# MDM_V3_LEDPad_D.net
KiCad netlist of a schematic drawn in EAGLE
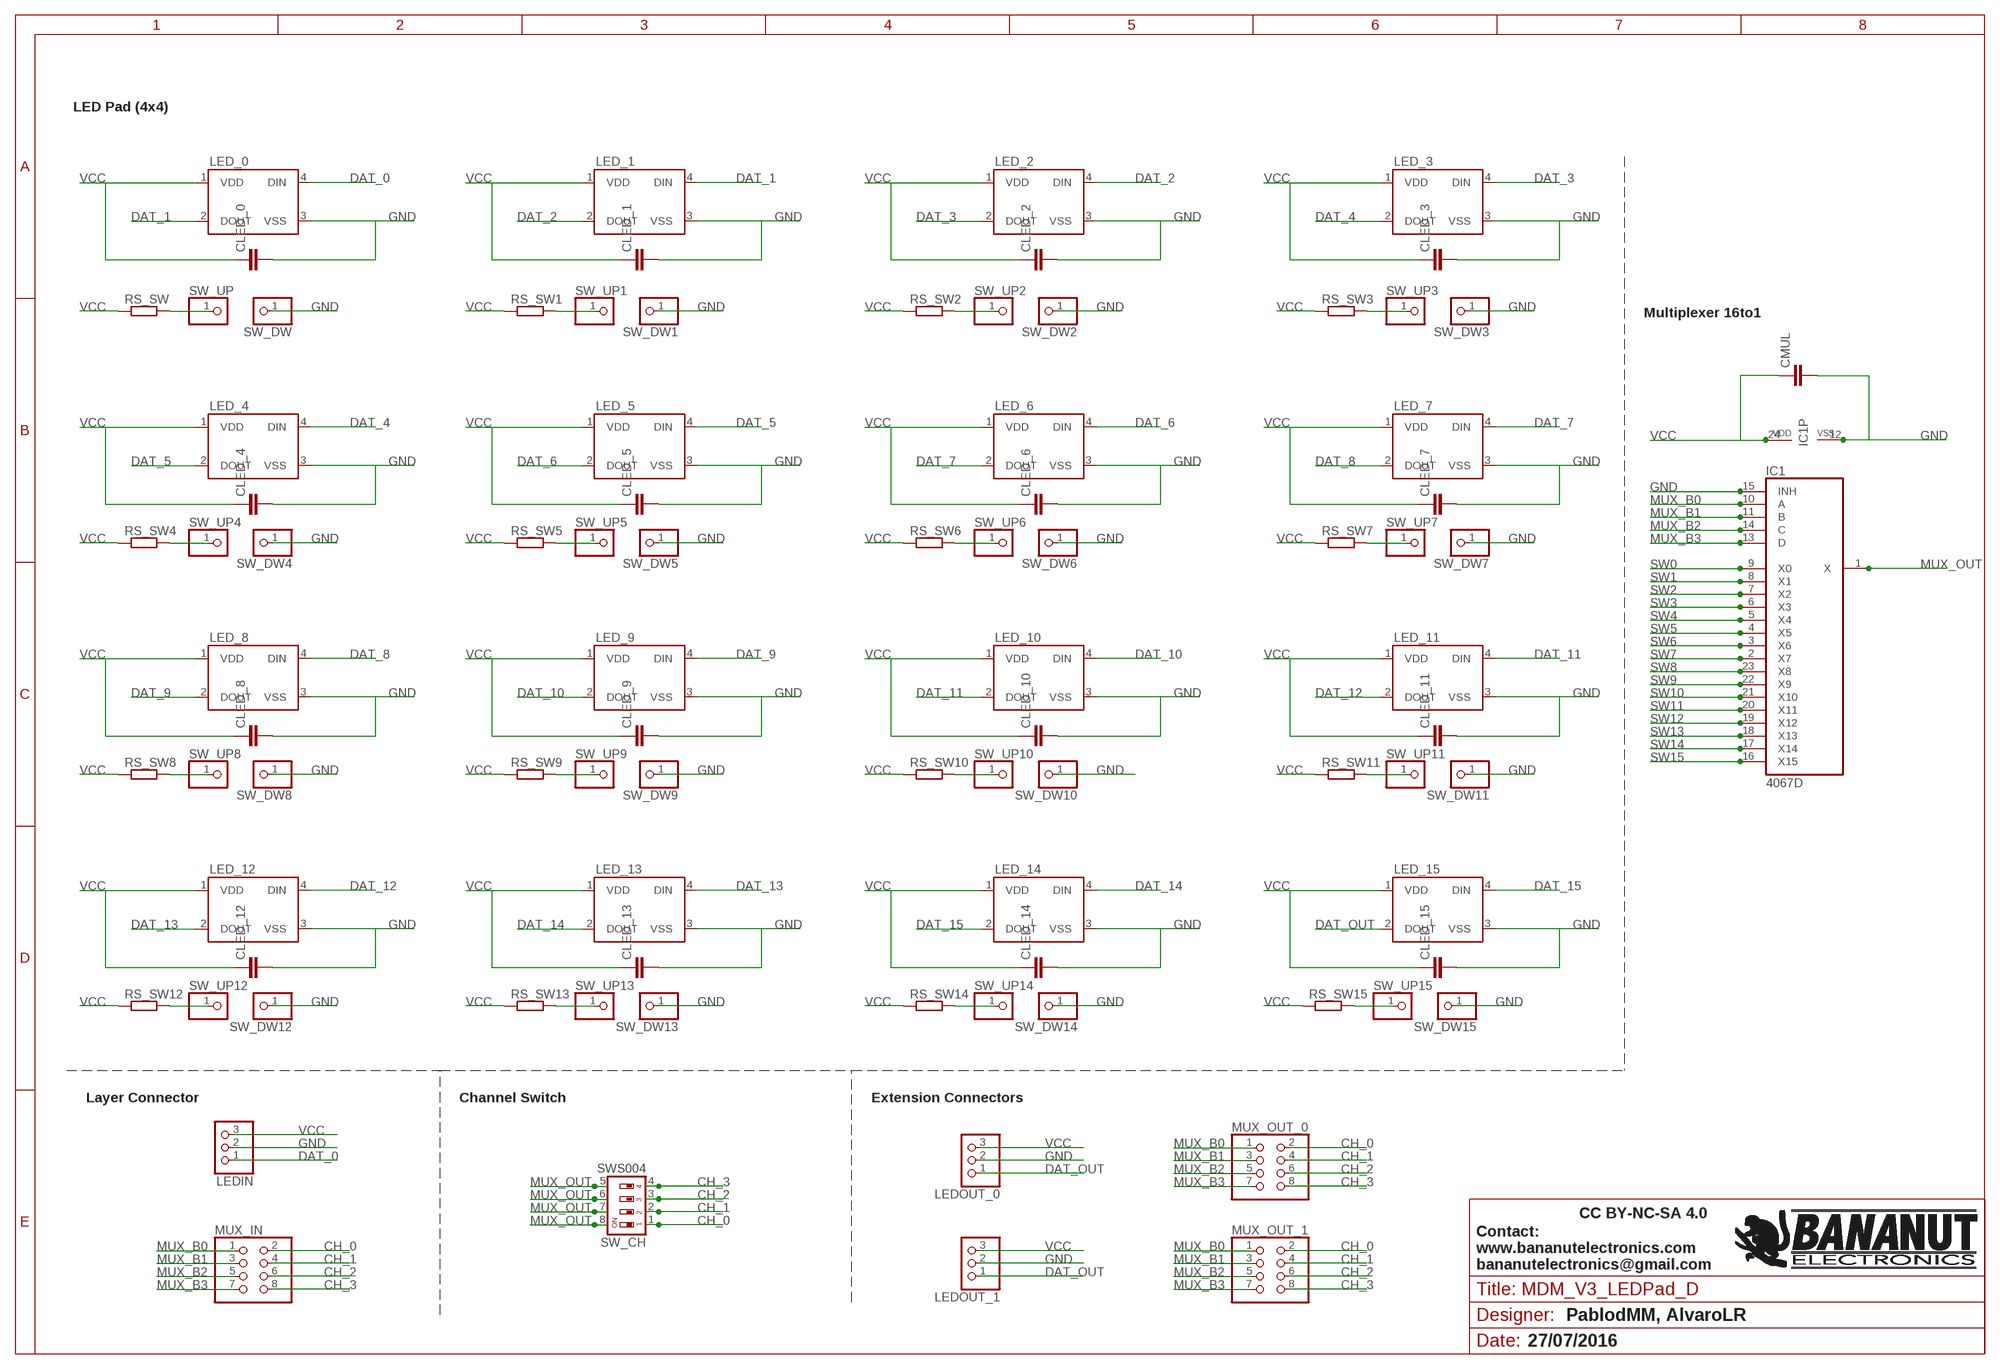
[diagram p0: schematic, sheet 1]

(export (version "E")
  (design (tool "Eeschema 10.0.6"))
  (components
    (comp (ref "CLED_0")
      (value "C-EUC1206K")
      (footprint "eagle-import:C1206K")
      (libsource (lib "eagle-import") (part "C-EUC1206K"))
    )
    (comp (ref "CLED_1")
      (value "C-EUC1206K")
      (footprint "eagle-import:C1206K")
      (libsource (lib "eagle-import") (part "C-EUC1206K"))
    )
    (comp (ref "CLED_2")
      (value "C-EUC1206K")
      (footprint "eagle-import:C1206K")
      (libsource (lib "eagle-import") (part "C-EUC1206K"))
    )
    (comp (ref "CLED_3")
      (value "C-EUC1206K")
      (footprint "eagle-import:C1206K")
      (libsource (lib "eagle-import") (part "C-EUC1206K"))
    )
    (comp (ref "CLED_4")
      (value "C-EUC1206K")
      (footprint "eagle-import:C1206K")
      (libsource (lib "eagle-import") (part "C-EUC1206K"))
    )
    (comp (ref "CLED_5")
      (value "C-EUC1206K")
      (footprint "eagle-import:C1206K")
      (libsource (lib "eagle-import") (part "C-EUC1206K"))
    )
    (comp (ref "CLED_6")
      (value "C-EUC1206K")
      (footprint "eagle-import:C1206K")
      (libsource (lib "eagle-import") (part "C-EUC1206K"))
    )
    (comp (ref "CLED_7")
      (value "C-EUC1206K")
      (footprint "eagle-import:C1206K")
      (libsource (lib "eagle-import") (part "C-EUC1206K"))
    )
    (comp (ref "CLED_8")
      (value "C-EUC1206K")
      (footprint "eagle-import:C1206K")
      (libsource (lib "eagle-import") (part "C-EUC1206K"))
    )
    (comp (ref "CLED_9")
      (value "C-EUC1206K")
      (footprint "eagle-import:C1206K")
      (libsource (lib "eagle-import") (part "C-EUC1206K"))
    )
    (comp (ref "CLED_10")
      (value "C-EUC1206K")
      (footprint "eagle-import:C1206K")
      (libsource (lib "eagle-import") (part "C-EUC1206K"))
    )
    (comp (ref "CLED_11")
      (value "C-EUC1206K")
      (footprint "eagle-import:C1206K")
      (libsource (lib "eagle-import") (part "C-EUC1206K"))
    )
    (comp (ref "CLED_12")
      (value "C-EUC1206K")
      (footprint "eagle-import:C1206K")
      (libsource (lib "eagle-import") (part "C-EUC1206K"))
    )
    (comp (ref "CLED_13")
      (value "C-EUC1206K")
      (footprint "eagle-import:C1206K")
      (libsource (lib "eagle-import") (part "C-EUC1206K"))
    )
    (comp (ref "CLED_14")
      (value "C-EUC1206K")
      (footprint "eagle-import:C1206K")
      (libsource (lib "eagle-import") (part "C-EUC1206K"))
    )
    (comp (ref "CLED_15")
      (value "C-EUC1206K")
      (footprint "eagle-import:C1206K")
      (libsource (lib "eagle-import") (part "C-EUC1206K"))
    )
    (comp (ref "CMUL")
      (value "C-EUC1206K")
      (footprint "eagle-import:C1206K")
      (libsource (lib "eagle-import") (part "C-EUC1206K"))
    )
    (comp (ref "IC1")
      (value "4067D")
      (footprint "eagle-import:SO24W")
      (libsource (lib "eagle-import") (part "4067D"))
    )
    (comp (ref "LEDIN")
      (value "PINHD-1X3")
      (footprint "eagle-import:1X03")
      (libsource (lib "eagle-import") (part "PINHD-1X3"))
    )
    (comp (ref "LEDOUT_0")
      (value "PINHD-1X3")
      (footprint "eagle-import:1X03")
      (libsource (lib "eagle-import") (part "PINHD-1X3"))
    )
    (comp (ref "LEDOUT_1")
      (value "PINHD-1X3")
      (footprint "eagle-import:1X03")
      (libsource (lib "eagle-import") (part "PINHD-1X3"))
    )
    (comp (ref "LED_0")
      (value "WS2812B")
      (footprint "eagle-import:WS2812B")
      (libsource (lib "eagle-import") (part "WS2812B"))
    )
    (comp (ref "LED_1")
      (value "WS2812B")
      (footprint "eagle-import:WS2812B")
      (libsource (lib "eagle-import") (part "WS2812B"))
    )
    (comp (ref "LED_2")
      (value "WS2812B")
      (footprint "eagle-import:WS2812B")
      (libsource (lib "eagle-import") (part "WS2812B"))
    )
    (comp (ref "LED_3")
      (value "WS2812B")
      (footprint "eagle-import:WS2812B")
      (libsource (lib "eagle-import") (part "WS2812B"))
    )
    (comp (ref "LED_4")
      (value "WS2812B")
      (footprint "eagle-import:WS2812B")
      (libsource (lib "eagle-import") (part "WS2812B"))
    )
    (comp (ref "LED_5")
      (value "WS2812B")
      (footprint "eagle-import:WS2812B")
      (libsource (lib "eagle-import") (part "WS2812B"))
    )
    (comp (ref "LED_6")
      (value "WS2812B")
      (footprint "eagle-import:WS2812B")
      (libsource (lib "eagle-import") (part "WS2812B"))
    )
    (comp (ref "LED_7")
      (value "WS2812B")
      (footprint "eagle-import:WS2812B")
      (libsource (lib "eagle-import") (part "WS2812B"))
    )
    (comp (ref "LED_8")
      (value "WS2812B")
      (footprint "eagle-import:WS2812B")
      (libsource (lib "eagle-import") (part "WS2812B"))
    )
    (comp (ref "LED_9")
      (value "WS2812B")
      (footprint "eagle-import:WS2812B")
      (libsource (lib "eagle-import") (part "WS2812B"))
    )
    (comp (ref "LED_10")
      (value "WS2812B")
      (footprint "eagle-import:WS2812B")
      (libsource (lib "eagle-import") (part "WS2812B"))
    )
    (comp (ref "LED_11")
      (value "WS2812B")
      (footprint "eagle-import:WS2812B")
      (libsource (lib "eagle-import") (part "WS2812B"))
    )
    (comp (ref "LED_12")
      (value "WS2812B")
      (footprint "eagle-import:WS2812B")
      (libsource (lib "eagle-import") (part "WS2812B"))
    )
    (comp (ref "LED_13")
      (value "WS2812B")
      (footprint "eagle-import:WS2812B")
      (libsource (lib "eagle-import") (part "WS2812B"))
    )
    (comp (ref "LED_14")
      (value "WS2812B")
      (footprint "eagle-import:WS2812B")
      (libsource (lib "eagle-import") (part "WS2812B"))
    )
    (comp (ref "LED_15")
      (value "WS2812B")
      (footprint "eagle-import:WS2812B")
      (libsource (lib "eagle-import") (part "WS2812B"))
    )
    (comp (ref "MUX_IN")
      (value "PINHD-2X4")
      (footprint "eagle-import:2X04")
      (libsource (lib "eagle-import") (part "PINHD-2X4"))
    )
    (comp (ref "MUX_OUT_0")
      (value "PINHD-2X4")
      (footprint "eagle-import:2X04")
      (libsource (lib "eagle-import") (part "PINHD-2X4"))
    )
    (comp (ref "MUX_OUT_1")
      (value "PINHD-2X4")
      (footprint "eagle-import:2X04")
      (libsource (lib "eagle-import") (part "PINHD-2X4"))
    )
    (comp (ref "RS_SW")
      (value "R-EU_R1206")
      (footprint "eagle-import:R1206")
      (libsource (lib "eagle-import") (part "R-EU_R1206"))
    )
    (comp (ref "RS_SW1")
      (value "R-EU_R1206")
      (footprint "eagle-import:R1206")
      (libsource (lib "eagle-import") (part "R-EU_R1206"))
    )
    (comp (ref "RS_SW2")
      (value "R-EU_R1206")
      (footprint "eagle-import:R1206")
      (libsource (lib "eagle-import") (part "R-EU_R1206"))
    )
    (comp (ref "RS_SW3")
      (value "R-EU_R1206")
      (footprint "eagle-import:R1206")
      (libsource (lib "eagle-import") (part "R-EU_R1206"))
    )
    (comp (ref "RS_SW4")
      (value "R-EU_R1206")
      (footprint "eagle-import:R1206")
      (libsource (lib "eagle-import") (part "R-EU_R1206"))
    )
    (comp (ref "RS_SW5")
      (value "R-EU_R1206")
      (footprint "eagle-import:R1206")
      (libsource (lib "eagle-import") (part "R-EU_R1206"))
    )
    (comp (ref "RS_SW6")
      (value "R-EU_R1206")
      (footprint "eagle-import:R1206")
      (libsource (lib "eagle-import") (part "R-EU_R1206"))
    )
    (comp (ref "RS_SW7")
      (value "R-EU_R1206")
      (footprint "eagle-import:R1206")
      (libsource (lib "eagle-import") (part "R-EU_R1206"))
    )
    (comp (ref "RS_SW8")
      (value "R-EU_R1206")
      (footprint "eagle-import:R1206")
      (libsource (lib "eagle-import") (part "R-EU_R1206"))
    )
    (comp (ref "RS_SW9")
      (value "R-EU_R1206")
      (footprint "eagle-import:R1206")
      (libsource (lib "eagle-import") (part "R-EU_R1206"))
    )
    (comp (ref "RS_SW10")
      (value "R-EU_R1206")
      (footprint "eagle-import:R1206")
      (libsource (lib "eagle-import") (part "R-EU_R1206"))
    )
    (comp (ref "RS_SW11")
      (value "R-EU_R1206")
      (footprint "eagle-import:R1206")
      (libsource (lib "eagle-import") (part "R-EU_R1206"))
    )
    (comp (ref "RS_SW12")
      (value "R-EU_R1206")
      (footprint "eagle-import:R1206")
      (libsource (lib "eagle-import") (part "R-EU_R1206"))
    )
    (comp (ref "RS_SW13")
      (value "R-EU_R1206")
      (footprint "eagle-import:R1206")
      (libsource (lib "eagle-import") (part "R-EU_R1206"))
    )
    (comp (ref "RS_SW14")
      (value "R-EU_R1206")
      (footprint "eagle-import:R1206")
      (libsource (lib "eagle-import") (part "R-EU_R1206"))
    )
    (comp (ref "RS_SW15")
      (value "R-EU_R1206")
      (footprint "eagle-import:R1206")
      (libsource (lib "eagle-import") (part "R-EU_R1206"))
    )
    (comp (ref "SW_CH")
      (value "SWS004")
      (footprint "eagle-import:SMS-004")
      (libsource (lib "eagle-import") (part "SWS004"))
    )
    (comp (ref "SW_DW")
      (value "PINHD-1X1CB")
      (footprint "eagle-import:1X01-CLEANBIG")
      (libsource (lib "eagle-import") (part "PINHD-1X1CB"))
    )
    (comp (ref "SW_DW1")
      (value "PINHD-1X1CB")
      (footprint "eagle-import:1X01-CLEANBIG")
      (libsource (lib "eagle-import") (part "PINHD-1X1CB"))
    )
    (comp (ref "SW_DW2")
      (value "PINHD-1X1CB")
      (footprint "eagle-import:1X01-CLEANBIG")
      (libsource (lib "eagle-import") (part "PINHD-1X1CB"))
    )
    (comp (ref "SW_DW3")
      (value "PINHD-1X1CB")
      (footprint "eagle-import:1X01-CLEANBIG")
      (libsource (lib "eagle-import") (part "PINHD-1X1CB"))
    )
    (comp (ref "SW_DW4")
      (value "PINHD-1X1CB")
      (footprint "eagle-import:1X01-CLEANBIG")
      (libsource (lib "eagle-import") (part "PINHD-1X1CB"))
    )
    (comp (ref "SW_DW5")
      (value "PINHD-1X1CB")
      (footprint "eagle-import:1X01-CLEANBIG")
      (libsource (lib "eagle-import") (part "PINHD-1X1CB"))
    )
    (comp (ref "SW_DW6")
      (value "PINHD-1X1CB")
      (footprint "eagle-import:1X01-CLEANBIG")
      (libsource (lib "eagle-import") (part "PINHD-1X1CB"))
    )
    (comp (ref "SW_DW7")
      (value "PINHD-1X1CB")
      (footprint "eagle-import:1X01-CLEANBIG")
      (libsource (lib "eagle-import") (part "PINHD-1X1CB"))
    )
    (comp (ref "SW_DW8")
      (value "PINHD-1X1CB")
      (footprint "eagle-import:1X01-CLEANBIG")
      (libsource (lib "eagle-import") (part "PINHD-1X1CB"))
    )
    (comp (ref "SW_DW9")
      (value "PINHD-1X1CB")
      (footprint "eagle-import:1X01-CLEANBIG")
      (libsource (lib "eagle-import") (part "PINHD-1X1CB"))
    )
    (comp (ref "SW_DW10")
      (value "PINHD-1X1CB")
      (footprint "eagle-import:1X01-CLEANBIG")
      (libsource (lib "eagle-import") (part "PINHD-1X1CB"))
    )
    (comp (ref "SW_DW11")
      (value "PINHD-1X1CB")
      (footprint "eagle-import:1X01-CLEANBIG")
      (libsource (lib "eagle-import") (part "PINHD-1X1CB"))
    )
    (comp (ref "SW_DW12")
      (value "PINHD-1X1CB")
      (footprint "eagle-import:1X01-CLEANBIG")
      (libsource (lib "eagle-import") (part "PINHD-1X1CB"))
    )
    (comp (ref "SW_DW13")
      (value "PINHD-1X1CB")
      (footprint "eagle-import:1X01-CLEANBIG")
      (libsource (lib "eagle-import") (part "PINHD-1X1CB"))
    )
    (comp (ref "SW_DW14")
      (value "PINHD-1X1CB")
      (footprint "eagle-import:1X01-CLEANBIG")
      (libsource (lib "eagle-import") (part "PINHD-1X1CB"))
    )
    (comp (ref "SW_DW15")
      (value "PINHD-1X1CB")
      (footprint "eagle-import:1X01-CLEANBIG")
      (libsource (lib "eagle-import") (part "PINHD-1X1CB"))
    )
    (comp (ref "SW_UP")
      (value "PINHD-1X1CB")
      (footprint "eagle-import:1X01-CLEANBIG")
      (libsource (lib "eagle-import") (part "PINHD-1X1CB"))
    )
    (comp (ref "SW_UP1")
      (value "PINHD-1X1CB")
      (footprint "eagle-import:1X01-CLEANBIG")
      (libsource (lib "eagle-import") (part "PINHD-1X1CB"))
    )
    (comp (ref "SW_UP2")
      (value "PINHD-1X1CB")
      (footprint "eagle-import:1X01-CLEANBIG")
      (libsource (lib "eagle-import") (part "PINHD-1X1CB"))
    )
    (comp (ref "SW_UP3")
      (value "PINHD-1X1CB")
      (footprint "eagle-import:1X01-CLEANBIG")
      (libsource (lib "eagle-import") (part "PINHD-1X1CB"))
    )
    (comp (ref "SW_UP4")
      (value "PINHD-1X1CB")
      (footprint "eagle-import:1X01-CLEANBIG")
      (libsource (lib "eagle-import") (part "PINHD-1X1CB"))
    )
    (comp (ref "SW_UP5")
      (value "PINHD-1X1CB")
      (footprint "eagle-import:1X01-CLEANBIG")
      (libsource (lib "eagle-import") (part "PINHD-1X1CB"))
    )
    (comp (ref "SW_UP6")
      (value "PINHD-1X1CB")
      (footprint "eagle-import:1X01-CLEANBIG")
      (libsource (lib "eagle-import") (part "PINHD-1X1CB"))
    )
    (comp (ref "SW_UP7")
      (value "PINHD-1X1CB")
      (footprint "eagle-import:1X01-CLEANBIG")
      (libsource (lib "eagle-import") (part "PINHD-1X1CB"))
    )
    (comp (ref "SW_UP8")
      (value "PINHD-1X1CB")
      (footprint "eagle-import:1X01-CLEANBIG")
      (libsource (lib "eagle-import") (part "PINHD-1X1CB"))
    )
    (comp (ref "SW_UP9")
      (value "PINHD-1X1CB")
      (footprint "eagle-import:1X01-CLEANBIG")
      (libsource (lib "eagle-import") (part "PINHD-1X1CB"))
    )
    (comp (ref "SW_UP10")
      (value "PINHD-1X1CB")
      (footprint "eagle-import:1X01-CLEANBIG")
      (libsource (lib "eagle-import") (part "PINHD-1X1CB"))
    )
    (comp (ref "SW_UP11")
      (value "PINHD-1X1CB")
      (footprint "eagle-import:1X01-CLEANBIG")
      (libsource (lib "eagle-import") (part "PINHD-1X1CB"))
    )
    (comp (ref "SW_UP12")
      (value "PINHD-1X1CB")
      (footprint "eagle-import:1X01-CLEANBIG")
      (libsource (lib "eagle-import") (part "PINHD-1X1CB"))
    )
    (comp (ref "SW_UP13")
      (value "PINHD-1X1CB")
      (footprint "eagle-import:1X01-CLEANBIG")
      (libsource (lib "eagle-import") (part "PINHD-1X1CB"))
    )
    (comp (ref "SW_UP14")
      (value "PINHD-1X1CB")
      (footprint "eagle-import:1X01-CLEANBIG")
      (libsource (lib "eagle-import") (part "PINHD-1X1CB"))
    )
    (comp (ref "SW_UP15")
      (value "PINHD-1X1CB")
      (footprint "eagle-import:1X01-CLEANBIG")
      (libsource (lib "eagle-import") (part "PINHD-1X1CB"))
    )
  )
  (nets
    (net (code "1") (name "/CH_0") (class "Default")
      (node (ref "MUX_IN") (pin "2") (pinfunction "2_2") (pintype "passive"))
      (node (ref "MUX_OUT_0") (pin "2") (pinfunction "2_2") (pintype "passive"))
      (node (ref "MUX_OUT_1") (pin "2") (pinfunction "2_2") (pintype "passive"))
      (node (ref "SW_CH") (pin "1") (pinfunction "1_1") (pintype "passive"))
    )
    (net (code "2") (name "/CH_1") (class "Default")
      (node (ref "MUX_IN") (pin "4") (pinfunction "4_4") (pintype "passive"))
      (node (ref "MUX_OUT_0") (pin "4") (pinfunction "4_4") (pintype "passive"))
      (node (ref "MUX_OUT_1") (pin "4") (pinfunction "4_4") (pintype "passive"))
      (node (ref "SW_CH") (pin "2") (pinfunction "2_2") (pintype "passive"))
    )
    (net (code "3") (name "/CH_2") (class "Default")
      (node (ref "MUX_IN") (pin "6") (pinfunction "6_6") (pintype "passive"))
      (node (ref "MUX_OUT_0") (pin "6") (pinfunction "6_6") (pintype "passive"))
      (node (ref "MUX_OUT_1") (pin "6") (pinfunction "6_6") (pintype "passive"))
      (node (ref "SW_CH") (pin "3") (pinfunction "3_3") (pintype "passive"))
    )
    (net (code "4") (name "/CH_3") (class "Default")
      (node (ref "MUX_IN") (pin "8") (pinfunction "8_8") (pintype "passive"))
      (node (ref "MUX_OUT_0") (pin "8") (pinfunction "8_8") (pintype "passive"))
      (node (ref "MUX_OUT_1") (pin "8") (pinfunction "8_8") (pintype "passive"))
      (node (ref "SW_CH") (pin "4") (pinfunction "4_4") (pintype "passive"))
    )
    (net (code "5") (name "/DAT_0") (class "Default")
      (node (ref "LEDIN") (pin "1") (pinfunction "1_1") (pintype "passive"))
      (node (ref "LED_0") (pin "4") (pinfunction "DIN_4") (pintype "input"))
    )
    (net (code "6") (name "/DAT_1") (class "Default")
      (node (ref "LED_0") (pin "2") (pinfunction "DOUT_2") (pintype "output"))
      (node (ref "LED_1") (pin "4") (pinfunction "DIN_4") (pintype "input"))
    )
    (net (code "7") (name "/DAT_2") (class "Default")
      (node (ref "LED_1") (pin "2") (pinfunction "DOUT_2") (pintype "output"))
      (node (ref "LED_2") (pin "4") (pinfunction "DIN_4") (pintype "input"))
    )
    (net (code "8") (name "/DAT_3") (class "Default")
      (node (ref "LED_2") (pin "2") (pinfunction "DOUT_2") (pintype "output"))
      (node (ref "LED_3") (pin "4") (pinfunction "DIN_4") (pintype "input"))
    )
    (net (code "9") (name "/DAT_4") (class "Default")
      (node (ref "LED_3") (pin "2") (pinfunction "DOUT_2") (pintype "output"))
      (node (ref "LED_4") (pin "4") (pinfunction "DIN_4") (pintype "input"))
    )
    (net (code "10") (name "/DAT_5") (class "Default")
      (node (ref "LED_4") (pin "2") (pinfunction "DOUT_2") (pintype "output"))
      (node (ref "LED_5") (pin "4") (pinfunction "DIN_4") (pintype "input"))
    )
    (net (code "11") (name "/DAT_6") (class "Default")
      (node (ref "LED_5") (pin "2") (pinfunction "DOUT_2") (pintype "output"))
      (node (ref "LED_6") (pin "4") (pinfunction "DIN_4") (pintype "input"))
    )
    (net (code "12") (name "/DAT_7") (class "Default")
      (node (ref "LED_6") (pin "2") (pinfunction "DOUT_2") (pintype "output"))
      (node (ref "LED_7") (pin "4") (pinfunction "DIN_4") (pintype "input"))
    )
    (net (code "13") (name "/DAT_8") (class "Default")
      (node (ref "LED_7") (pin "2") (pinfunction "DOUT_2") (pintype "output"))
      (node (ref "LED_8") (pin "4") (pinfunction "DIN_4") (pintype "input"))
    )
    (net (code "14") (name "/DAT_9") (class "Default")
      (node (ref "LED_8") (pin "2") (pinfunction "DOUT_2") (pintype "output"))
      (node (ref "LED_9") (pin "4") (pinfunction "DIN_4") (pintype "input"))
    )
    (net (code "15") (name "/DAT_10") (class "Default")
      (node (ref "LED_10") (pin "4") (pinfunction "DIN_4") (pintype "input"))
      (node (ref "LED_9") (pin "2") (pinfunction "DOUT_2") (pintype "output"))
    )
    (net (code "16") (name "/DAT_11") (class "Default")
      (node (ref "LED_10") (pin "2") (pinfunction "DOUT_2") (pintype "output"))
      (node (ref "LED_11") (pin "4") (pinfunction "DIN_4") (pintype "input"))
    )
    (net (code "17") (name "/DAT_12") (class "Default")
      (node (ref "LED_11") (pin "2") (pinfunction "DOUT_2") (pintype "output"))
      (node (ref "LED_12") (pin "4") (pinfunction "DIN_4") (pintype "input"))
    )
    (net (code "18") (name "/DAT_13") (class "Default")
      (node (ref "LED_12") (pin "2") (pinfunction "DOUT_2") (pintype "output"))
      (node (ref "LED_13") (pin "4") (pinfunction "DIN_4") (pintype "input"))
    )
    (net (code "19") (name "/DAT_14") (class "Default")
      (node (ref "LED_13") (pin "2") (pinfunction "DOUT_2") (pintype "output"))
      (node (ref "LED_14") (pin "4") (pinfunction "DIN_4") (pintype "input"))
    )
    (net (code "20") (name "/DAT_15") (class "Default")
      (node (ref "LED_14") (pin "2") (pinfunction "DOUT_2") (pintype "output"))
      (node (ref "LED_15") (pin "4") (pinfunction "DIN_4") (pintype "input"))
    )
    (net (code "21") (name "/DAT_OUT") (class "Default")
      (node (ref "LEDOUT_0") (pin "1") (pinfunction "1_1") (pintype "passive"))
      (node (ref "LEDOUT_1") (pin "1") (pinfunction "1_1") (pintype "passive"))
      (node (ref "LED_15") (pin "2") (pinfunction "DOUT_2") (pintype "output"))
    )
    (net (code "22") (name "/GND") (class "Default")
      (node (ref "CLED_0") (pin "2") (pinfunction "2_2") (pintype "passive"))
      (node (ref "CLED_1") (pin "2") (pinfunction "2_2") (pintype "passive"))
      (node (ref "CLED_10") (pin "2") (pinfunction "2_2") (pintype "passive"))
      (node (ref "CLED_11") (pin "2") (pinfunction "2_2") (pintype "passive"))
      (node (ref "CLED_12") (pin "2") (pinfunction "2_2") (pintype "passive"))
      (node (ref "CLED_13") (pin "2") (pinfunction "2_2") (pintype "passive"))
      (node (ref "CLED_14") (pin "2") (pinfunction "2_2") (pintype "passive"))
      (node (ref "CLED_15") (pin "2") (pinfunction "2_2") (pintype "passive"))
      (node (ref "CLED_2") (pin "2") (pinfunction "2_2") (pintype "passive"))
      (node (ref "CLED_3") (pin "2") (pinfunction "2_2") (pintype "passive"))
      (node (ref "CLED_4") (pin "2") (pinfunction "2_2") (pintype "passive"))
      (node (ref "CLED_5") (pin "2") (pinfunction "2_2") (pintype "passive"))
      (node (ref "CLED_6") (pin "2") (pinfunction "2_2") (pintype "passive"))
      (node (ref "CLED_7") (pin "2") (pinfunction "2_2") (pintype "passive"))
      (node (ref "CLED_8") (pin "2") (pinfunction "2_2") (pintype "passive"))
      (node (ref "CLED_9") (pin "2") (pinfunction "2_2") (pintype "passive"))
      (node (ref "CMUL") (pin "2") (pinfunction "2_2") (pintype "passive"))
      (node (ref "IC1") (pin "12") (pinfunction "VSS_12") (pintype "power_in"))
      (node (ref "IC1") (pin "15") (pinfunction "INH_15") (pintype "input"))
      (node (ref "LEDIN") (pin "2") (pinfunction "2_2") (pintype "passive"))
      (node (ref "LEDOUT_0") (pin "2") (pinfunction "2_2") (pintype "passive"))
      (node (ref "LEDOUT_1") (pin "2") (pinfunction "2_2") (pintype "passive"))
      (node (ref "LED_0") (pin "3") (pinfunction "VSS_3") (pintype "power_in"))
      (node (ref "LED_1") (pin "3") (pinfunction "VSS_3") (pintype "power_in"))
      (node (ref "LED_10") (pin "3") (pinfunction "VSS_3") (pintype "power_in"))
      (node (ref "LED_11") (pin "3") (pinfunction "VSS_3") (pintype "power_in"))
      (node (ref "LED_12") (pin "3") (pinfunction "VSS_3") (pintype "power_in"))
      (node (ref "LED_13") (pin "3") (pinfunction "VSS_3") (pintype "power_in"))
      (node (ref "LED_14") (pin "3") (pinfunction "VSS_3") (pintype "power_in"))
      (node (ref "LED_15") (pin "3") (pinfunction "VSS_3") (pintype "power_in"))
      (node (ref "LED_2") (pin "3") (pinfunction "VSS_3") (pintype "power_in"))
      (node (ref "LED_3") (pin "3") (pinfunction "VSS_3") (pintype "power_in"))
      (node (ref "LED_4") (pin "3") (pinfunction "VSS_3") (pintype "power_in"))
      (node (ref "LED_5") (pin "3") (pinfunction "VSS_3") (pintype "power_in"))
      (node (ref "LED_6") (pin "3") (pinfunction "VSS_3") (pintype "power_in"))
      (node (ref "LED_7") (pin "3") (pinfunction "VSS_3") (pintype "power_in"))
      (node (ref "LED_8") (pin "3") (pinfunction "VSS_3") (pintype "power_in"))
      (node (ref "LED_9") (pin "3") (pinfunction "VSS_3") (pintype "power_in"))
      (node (ref "SW_DW") (pin "1") (pinfunction "1_1") (pintype "passive"))
      (node (ref "SW_DW1") (pin "1") (pinfunction "1_1") (pintype "passive"))
      (node (ref "SW_DW10") (pin "1") (pinfunction "1_1") (pintype "passive"))
      (node (ref "SW_DW11") (pin "1") (pinfunction "1_1") (pintype "passive"))
      (node (ref "SW_DW12") (pin "1") (pinfunction "1_1") (pintype "passive"))
      (node (ref "SW_DW13") (pin "1") (pinfunction "1_1") (pintype "passive"))
      (node (ref "SW_DW14") (pin "1") (pinfunction "1_1") (pintype "passive"))
      (node (ref "SW_DW15") (pin "1") (pinfunction "1_1") (pintype "passive"))
      (node (ref "SW_DW2") (pin "1") (pinfunction "1_1") (pintype "passive"))
      (node (ref "SW_DW3") (pin "1") (pinfunction "1_1") (pintype "passive"))
      (node (ref "SW_DW4") (pin "1") (pinfunction "1_1") (pintype "passive"))
      (node (ref "SW_DW5") (pin "1") (pinfunction "1_1") (pintype "passive"))
      (node (ref "SW_DW6") (pin "1") (pinfunction "1_1") (pintype "passive"))
      (node (ref "SW_DW7") (pin "1") (pinfunction "1_1") (pintype "passive"))
      (node (ref "SW_DW8") (pin "1") (pinfunction "1_1") (pintype "passive"))
      (node (ref "SW_DW9") (pin "1") (pinfunction "1_1") (pintype "passive"))
    )
    (net (code "23") (name "/MUX_B0") (class "Default")
      (node (ref "IC1") (pin "10") (pinfunction "A_10") (pintype "input"))
      (node (ref "MUX_IN") (pin "1") (pinfunction "1_1") (pintype "passive"))
      (node (ref "MUX_OUT_0") (pin "1") (pinfunction "1_1") (pintype "passive"))
      (node (ref "MUX_OUT_1") (pin "1") (pinfunction "1_1") (pintype "passive"))
    )
    (net (code "24") (name "/MUX_B1") (class "Default")
      (node (ref "IC1") (pin "11") (pinfunction "B_11") (pintype "input"))
      (node (ref "MUX_IN") (pin "3") (pinfunction "3_3") (pintype "passive"))
      (node (ref "MUX_OUT_0") (pin "3") (pinfunction "3_3") (pintype "passive"))
      (node (ref "MUX_OUT_1") (pin "3") (pinfunction "3_3") (pintype "passive"))
    )
    (net (code "25") (name "/MUX_B2") (class "Default")
      (node (ref "IC1") (pin "14") (pinfunction "C_14") (pintype "input"))
      (node (ref "MUX_IN") (pin "5") (pinfunction "5_5") (pintype "passive"))
      (node (ref "MUX_OUT_0") (pin "5") (pinfunction "5_5") (pintype "passive"))
      (node (ref "MUX_OUT_1") (pin "5") (pinfunction "5_5") (pintype "passive"))
    )
    (net (code "26") (name "/MUX_B3") (class "Default")
      (node (ref "IC1") (pin "13") (pinfunction "D_13") (pintype "input"))
      (node (ref "MUX_IN") (pin "7") (pinfunction "7_7") (pintype "passive"))
      (node (ref "MUX_OUT_0") (pin "7") (pinfunction "7_7") (pintype "passive"))
      (node (ref "MUX_OUT_1") (pin "7") (pinfunction "7_7") (pintype "passive"))
    )
    (net (code "27") (name "/MUX_OUT") (class "Default")
      (node (ref "IC1") (pin "1") (pinfunction "X_1") (pintype "output"))
      (node (ref "SW_CH") (pin "5") (pinfunction "5_5") (pintype "passive"))
      (node (ref "SW_CH") (pin "6") (pinfunction "6_6") (pintype "passive"))
      (node (ref "SW_CH") (pin "7") (pinfunction "7_7") (pintype "passive"))
      (node (ref "SW_CH") (pin "8") (pinfunction "8_8") (pintype "passive"))
    )
    (net (code "28") (name "/SW0") (class "Default")
      (node (ref "IC1") (pin "9") (pinfunction "X0_9") (pintype "input"))
      (node (ref "RS_SW") (pin "2") (pinfunction "2_2") (pintype "passive"))
      (node (ref "SW_UP") (pin "1") (pinfunction "1_1") (pintype "passive"))
    )
    (net (code "29") (name "/SW1") (class "Default")
      (node (ref "IC1") (pin "8") (pinfunction "X1_8") (pintype "input"))
      (node (ref "RS_SW1") (pin "2") (pinfunction "2_2") (pintype "passive"))
      (node (ref "SW_UP1") (pin "1") (pinfunction "1_1") (pintype "passive"))
    )
    (net (code "30") (name "/SW2") (class "Default")
      (node (ref "IC1") (pin "7") (pinfunction "X2_7") (pintype "input"))
      (node (ref "RS_SW2") (pin "2") (pinfunction "2_2") (pintype "passive"))
      (node (ref "SW_UP2") (pin "1") (pinfunction "1_1") (pintype "passive"))
    )
    (net (code "31") (name "/SW3") (class "Default")
      (node (ref "IC1") (pin "6") (pinfunction "X3_6") (pintype "input"))
      (node (ref "RS_SW3") (pin "2") (pinfunction "2_2") (pintype "passive"))
      (node (ref "SW_UP3") (pin "1") (pinfunction "1_1") (pintype "passive"))
    )
    (net (code "32") (name "/SW4") (class "Default")
      (node (ref "IC1") (pin "5") (pinfunction "X4_5") (pintype "input"))
      (node (ref "RS_SW4") (pin "2") (pinfunction "2_2") (pintype "passive"))
      (node (ref "SW_UP4") (pin "1") (pinfunction "1_1") (pintype "passive"))
    )
    (net (code "33") (name "/SW5") (class "Default")
      (node (ref "IC1") (pin "4") (pinfunction "X5_4") (pintype "input"))
      (node (ref "RS_SW5") (pin "2") (pinfunction "2_2") (pintype "passive"))
      (node (ref "SW_UP5") (pin "1") (pinfunction "1_1") (pintype "passive"))
    )
    (net (code "34") (name "/SW6") (class "Default")
      (node (ref "IC1") (pin "3") (pinfunction "X6_3") (pintype "input"))
      (node (ref "RS_SW6") (pin "2") (pinfunction "2_2") (pintype "passive"))
      (node (ref "SW_UP6") (pin "1") (pinfunction "1_1") (pintype "passive"))
    )
    (net (code "35") (name "/SW7") (class "Default")
      (node (ref "IC1") (pin "2") (pinfunction "X7_2") (pintype "input"))
      (node (ref "RS_SW7") (pin "2") (pinfunction "2_2") (pintype "passive"))
      (node (ref "SW_UP7") (pin "1") (pinfunction "1_1") (pintype "passive"))
    )
    (net (code "36") (name "/SW8") (class "Default")
      (node (ref "IC1") (pin "23") (pinfunction "X8_23") (pintype "input"))
      (node (ref "RS_SW8") (pin "2") (pinfunction "2_2") (pintype "passive"))
      (node (ref "SW_UP8") (pin "1") (pinfunction "1_1") (pintype "passive"))
    )
    (net (code "37") (name "/SW9") (class "Default")
      (node (ref "IC1") (pin "22") (pinfunction "X9_22") (pintype "input"))
      (node (ref "RS_SW9") (pin "2") (pinfunction "2_2") (pintype "passive"))
      (node (ref "SW_UP9") (pin "1") (pinfunction "1_1") (pintype "passive"))
    )
    (net (code "38") (name "/SW10") (class "Default")
      (node (ref "IC1") (pin "21") (pinfunction "X10_21") (pintype "input"))
      (node (ref "RS_SW10") (pin "2") (pinfunction "2_2") (pintype "passive"))
      (node (ref "SW_UP10") (pin "1") (pinfunction "1_1") (pintype "passive"))
    )
    (net (code "39") (name "/SW11") (class "Default")
      (node (ref "IC1") (pin "20") (pinfunction "X11_20") (pintype "input"))
      (node (ref "RS_SW11") (pin "2") (pinfunction "2_2") (pintype "passive"))
      (node (ref "SW_UP11") (pin "1") (pinfunction "1_1") (pintype "passive"))
    )
    (net (code "40") (name "/SW12") (class "Default")
      (node (ref "IC1") (pin "19") (pinfunction "X12_19") (pintype "input"))
      (node (ref "RS_SW12") (pin "2") (pinfunction "2_2") (pintype "passive"))
      (node (ref "SW_UP12") (pin "1") (pinfunction "1_1") (pintype "passive"))
    )
    (net (code "41") (name "/SW13") (class "Default")
      (node (ref "IC1") (pin "18") (pinfunction "X13_18") (pintype "input"))
      (node (ref "RS_SW13") (pin "2") (pinfunction "2_2") (pintype "passive"))
      (node (ref "SW_UP13") (pin "1") (pinfunction "1_1") (pintype "passive"))
    )
    (net (code "42") (name "/SW14") (class "Default")
      (node (ref "IC1") (pin "17") (pinfunction "X14_17") (pintype "input"))
      (node (ref "RS_SW14") (pin "2") (pinfunction "2_2") (pintype "passive"))
      (node (ref "SW_UP14") (pin "1") (pinfunction "1_1") (pintype "passive"))
    )
    (net (code "43") (name "/SW15") (class "Default")
      (node (ref "IC1") (pin "16") (pinfunction "X15_16") (pintype "input"))
      (node (ref "RS_SW15") (pin "2") (pinfunction "2_2") (pintype "passive"))
      (node (ref "SW_UP15") (pin "1") (pinfunction "1_1") (pintype "passive"))
    )
    (net (code "44") (name "/VCC") (class "Default")
      (node (ref "CLED_0") (pin "1") (pinfunction "1_1") (pintype "passive"))
      (node (ref "CLED_1") (pin "1") (pinfunction "1_1") (pintype "passive"))
      (node (ref "CLED_10") (pin "1") (pinfunction "1_1") (pintype "passive"))
      (node (ref "CLED_11") (pin "1") (pinfunction "1_1") (pintype "passive"))
      (node (ref "CLED_12") (pin "1") (pinfunction "1_1") (pintype "passive"))
      (node (ref "CLED_13") (pin "1") (pinfunction "1_1") (pintype "passive"))
      (node (ref "CLED_14") (pin "1") (pinfunction "1_1") (pintype "passive"))
      (node (ref "CLED_15") (pin "1") (pinfunction "1_1") (pintype "passive"))
      (node (ref "CLED_2") (pin "1") (pinfunction "1_1") (pintype "passive"))
      (node (ref "CLED_3") (pin "1") (pinfunction "1_1") (pintype "passive"))
      (node (ref "CLED_4") (pin "1") (pinfunction "1_1") (pintype "passive"))
      (node (ref "CLED_5") (pin "1") (pinfunction "1_1") (pintype "passive"))
      (node (ref "CLED_6") (pin "1") (pinfunction "1_1") (pintype "passive"))
      (node (ref "CLED_7") (pin "1") (pinfunction "1_1") (pintype "passive"))
      (node (ref "CLED_8") (pin "1") (pinfunction "1_1") (pintype "passive"))
      (node (ref "CLED_9") (pin "1") (pinfunction "1_1") (pintype "passive"))
      (node (ref "CMUL") (pin "1") (pinfunction "1_1") (pintype "passive"))
      (node (ref "IC1") (pin "24") (pinfunction "VDD_24") (pintype "power_in"))
      (node (ref "LEDIN") (pin "3") (pinfunction "3_3") (pintype "passive"))
      (node (ref "LEDOUT_0") (pin "3") (pinfunction "3_3") (pintype "passive"))
      (node (ref "LEDOUT_1") (pin "3") (pinfunction "3_3") (pintype "passive"))
      (node (ref "LED_0") (pin "1") (pinfunction "VDD_1") (pintype "power_in"))
      (node (ref "LED_1") (pin "1") (pinfunction "VDD_1") (pintype "power_in"))
      (node (ref "LED_10") (pin "1") (pinfunction "VDD_1") (pintype "power_in"))
      (node (ref "LED_11") (pin "1") (pinfunction "VDD_1") (pintype "power_in"))
      (node (ref "LED_12") (pin "1") (pinfunction "VDD_1") (pintype "power_in"))
      (node (ref "LED_13") (pin "1") (pinfunction "VDD_1") (pintype "power_in"))
      (node (ref "LED_14") (pin "1") (pinfunction "VDD_1") (pintype "power_in"))
      (node (ref "LED_15") (pin "1") (pinfunction "VDD_1") (pintype "power_in"))
      (node (ref "LED_2") (pin "1") (pinfunction "VDD_1") (pintype "power_in"))
      (node (ref "LED_3") (pin "1") (pinfunction "VDD_1") (pintype "power_in"))
      (node (ref "LED_4") (pin "1") (pinfunction "VDD_1") (pintype "power_in"))
      (node (ref "LED_5") (pin "1") (pinfunction "VDD_1") (pintype "power_in"))
      (node (ref "LED_6") (pin "1") (pinfunction "VDD_1") (pintype "power_in"))
      (node (ref "LED_7") (pin "1") (pinfunction "VDD_1") (pintype "power_in"))
      (node (ref "LED_8") (pin "1") (pinfunction "VDD_1") (pintype "power_in"))
      (node (ref "LED_9") (pin "1") (pinfunction "VDD_1") (pintype "power_in"))
      (node (ref "RS_SW") (pin "1") (pinfunction "1_1") (pintype "passive"))
      (node (ref "RS_SW1") (pin "1") (pinfunction "1_1") (pintype "passive"))
      (node (ref "RS_SW10") (pin "1") (pinfunction "1_1") (pintype "passive"))
      (node (ref "RS_SW11") (pin "1") (pinfunction "1_1") (pintype "passive"))
      (node (ref "RS_SW12") (pin "1") (pinfunction "1_1") (pintype "passive"))
      (node (ref "RS_SW13") (pin "1") (pinfunction "1_1") (pintype "passive"))
      (node (ref "RS_SW14") (pin "1") (pinfunction "1_1") (pintype "passive"))
      (node (ref "RS_SW15") (pin "1") (pinfunction "1_1") (pintype "passive"))
      (node (ref "RS_SW2") (pin "1") (pinfunction "1_1") (pintype "passive"))
      (node (ref "RS_SW3") (pin "1") (pinfunction "1_1") (pintype "passive"))
      (node (ref "RS_SW4") (pin "1") (pinfunction "1_1") (pintype "passive"))
      (node (ref "RS_SW5") (pin "1") (pinfunction "1_1") (pintype "passive"))
      (node (ref "RS_SW6") (pin "1") (pinfunction "1_1") (pintype "passive"))
      (node (ref "RS_SW7") (pin "1") (pinfunction "1_1") (pintype "passive"))
      (node (ref "RS_SW8") (pin "1") (pinfunction "1_1") (pintype "passive"))
      (node (ref "RS_SW9") (pin "1") (pinfunction "1_1") (pintype "passive"))
    )
  )
)
